# protoboard.net
KiCad netlist of a schematic drawn in EAGLE
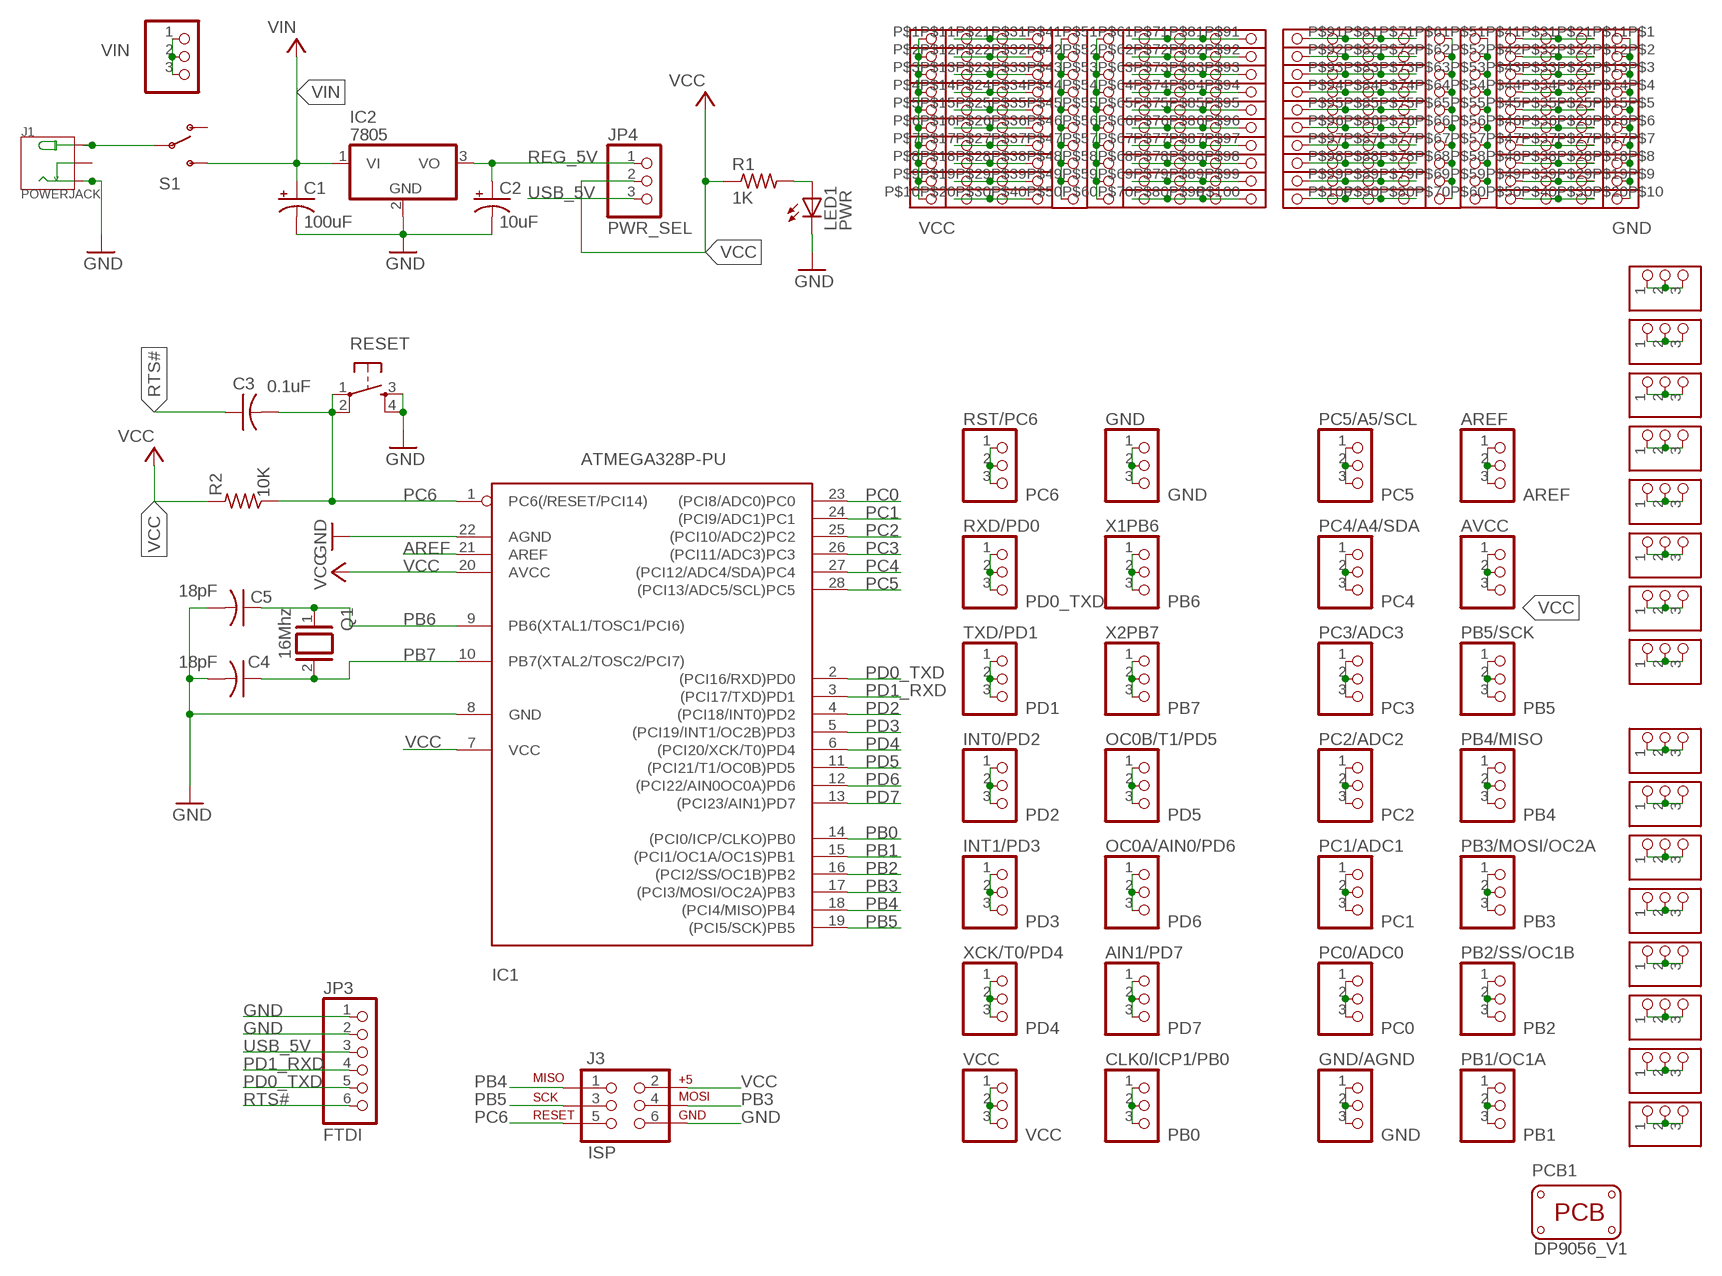
[diagram p0: schematic, sheet 1]

(export (version "E")
  (design (tool "Eeschema 10.0.6"))
  (components
    (comp (ref "AIN1/PD7")
      (value "PINHD-1X3")
      (footprint "eagle-import:1X03")
      (libsource (lib "eagle-import") (part "ubiyubix_PINHD-1X3"))
    )
    (comp (ref "AREF")
      (value "PINHD-1X3")
      (footprint "eagle-import:1X03")
      (libsource (lib "eagle-import") (part "ubiyubix_PINHD-1X3"))
    )
    (comp (ref "AVCC")
      (value "PINHD-1X3")
      (footprint "eagle-import:1X03")
      (libsource (lib "eagle-import") (part "ubiyubix_PINHD-1X3"))
    )
    (comp (ref "C1")
      (value "100uF")
      (footprint "eagle-import:CPOL-RADIAL-100UF-25V")
      (libsource (lib "eagle-import") (part "CAP_POLPTH1"))
    )
    (comp (ref "C2")
      (value "10uF")
      (footprint "eagle-import:CPOL-RADIAL-10UF-25V")
      (libsource (lib "eagle-import") (part "CAP_POLPTH2"))
    )
    (comp (ref "C3")
      (value "0.1uF")
      (footprint "eagle-import:C025-025X050")
      (libsource (lib "eagle-import") (part "C-US025-025X050"))
    )
    (comp (ref "C4")
      (value "18pF")
      (footprint "eagle-import:C025-025X050")
      (libsource (lib "eagle-import") (part "C-US025-025X050"))
    )
    (comp (ref "C5")
      (value "18pF")
      (footprint "eagle-import:C025-025X050")
      (libsource (lib "eagle-import") (part "C-US025-025X050"))
    )
    (comp (ref "CLK0/ICP1/PB0")
      (value "PINHD-1X3")
      (footprint "eagle-import:1X03")
      (libsource (lib "eagle-import") (part "ubiyubix_PINHD-1X3"))
    )
    (comp (ref "GND")
      (value "PINHD-1X3")
      (footprint "eagle-import:1X03")
      (libsource (lib "eagle-import") (part "ubiyubix_PINHD-1X3"))
    )
    (comp (ref "GND/AGND")
      (value "PINHD-1X3")
      (footprint "eagle-import:1X03")
      (libsource (lib "eagle-import") (part "ubiyubix_PINHD-1X3"))
    )
    (comp (ref "IC1")
      (value "ATMEGA328P-PU")
      (footprint "eagle-import:DIL28-3")
      (libsource (lib "eagle-import") (part "ATMEGA168P-20"))
    )
    (comp (ref "IC2")
      (value "7805")
      (footprint "eagle-import:TO220H")
      (libsource (lib "eagle-import") (part "78T05"))
    )
    (comp (ref "INT0/PD2")
      (value "PINHD-1X3")
      (footprint "eagle-import:1X03")
      (libsource (lib "eagle-import") (part "ubiyubix_PINHD-1X3"))
    )
    (comp (ref "INT1/PD3")
      (value "PINHD-1X3")
      (footprint "eagle-import:1X03")
      (libsource (lib "eagle-import") (part "ubiyubix_PINHD-1X3"))
    )
    (comp (ref "J1")
      (value "POWERJACK")
      (footprint "eagle-import:PW-3P-2.1")
      (libsource (lib "eagle-import") (part "JACK-DC-3P-3410020P1"))
    )
    (comp (ref "J3")
      (value "ISP")
      (footprint "eagle-import:2X3")
      (libsource (lib "eagle-import") (part "AVR_SPI_PRG_6PTH"))
    )
    (comp (ref "JP3")
      (value "FTDI")
      (footprint "eagle-import:1X06")
      (libsource (lib "eagle-import") (part "PINHD-1X6"))
    )
    (comp (ref "JP4")
      (value "PWR_SEL")
      (footprint "eagle-import:1X03")
      (libsource (lib "eagle-import") (part "PINHD-1X3"))
    )
    (comp (ref "LED1")
      (value "PWR")
      (footprint "eagle-import:LED3MM")
      (libsource (lib "eagle-import") (part "LED3MM"))
    )
    (comp (ref "OC0A/AIN0/PD6")
      (value "PINHD-1X3")
      (footprint "eagle-import:1X03")
      (libsource (lib "eagle-import") (part "ubiyubix_PINHD-1X3"))
    )
    (comp (ref "OC0B/T1/PD5")
      (value "PINHD-1X3")
      (footprint "eagle-import:1X03")
      (libsource (lib "eagle-import") (part "ubiyubix_PINHD-1X3"))
    )
    (comp (ref "PB1/OC1A")
      (value "PINHD-1X3")
      (footprint "eagle-import:1X03")
      (libsource (lib "eagle-import") (part "ubiyubix_PINHD-1X3"))
    )
    (comp (ref "PB2/SS/OC1B")
      (value "PINHD-1X3")
      (footprint "eagle-import:1X03")
      (libsource (lib "eagle-import") (part "ubiyubix_PINHD-1X3"))
    )
    (comp (ref "PB3/MOSI/OC2A")
      (value "PINHD-1X3")
      (footprint "eagle-import:1X03")
      (libsource (lib "eagle-import") (part "ubiyubix_PINHD-1X3"))
    )
    (comp (ref "PB4/MISO")
      (value "PINHD-1X3")
      (footprint "eagle-import:1X03")
      (libsource (lib "eagle-import") (part "ubiyubix_PINHD-1X3"))
    )
    (comp (ref "PB5/SCK")
      (value "PINHD-1X3")
      (footprint "eagle-import:1X03")
      (libsource (lib "eagle-import") (part "ubiyubix_PINHD-1X3"))
    )
    (comp (ref "PC0/ADC0")
      (value "PINHD-1X3")
      (footprint "eagle-import:1X03")
      (libsource (lib "eagle-import") (part "ubiyubix_PINHD-1X3"))
    )
    (comp (ref "PC1/ADC1")
      (value "PINHD-1X3")
      (footprint "eagle-import:1X03")
      (libsource (lib "eagle-import") (part "ubiyubix_PINHD-1X3"))
    )
    (comp (ref "PC2/ADC2")
      (value "PINHD-1X3")
      (footprint "eagle-import:1X03")
      (libsource (lib "eagle-import") (part "ubiyubix_PINHD-1X3"))
    )
    (comp (ref "PC3/ADC3")
      (value "PINHD-1X3")
      (footprint "eagle-import:1X03")
      (libsource (lib "eagle-import") (part "ubiyubix_PINHD-1X3"))
    )
    (comp (ref "PC4/A4/SDA")
      (value "PINHD-1X3")
      (footprint "eagle-import:1X03")
      (libsource (lib "eagle-import") (part "ubiyubix_PINHD-1X3"))
    )
    (comp (ref "PC5/A5/SCL")
      (value "PINHD-1X3")
      (footprint "eagle-import:1X03")
      (libsource (lib "eagle-import") (part "ubiyubix_PINHD-1X3"))
    )
    (comp (ref "PCB1")
      (value "PCB_DP_RECTANGLE-56X90")
      (footprint "eagle-import:DP9056_V1")
      (libsource (lib "eagle-import") (part "PCB_DP_RECTANGLE-56X90"))
    )
    (comp (ref "Q1")
      (value "16Mhz")
      (footprint "eagle-import:QS")
      (libsource (lib "eagle-import") (part "XTAL/S"))
    )
    (comp (ref "R1")
      (value "1K")
      (footprint "eagle-import:0207_7")
      (libsource (lib "eagle-import") (part "RESISTOR-1/4W"))
    )
    (comp (ref "R2")
      (value "10K")
      (footprint "eagle-import:0207_7")
      (libsource (lib "eagle-import") (part "RESISTOR-1/4W"))
    )
    (comp (ref "RESET")
      (value "TAC_SWITCHPTH")
      (footprint "eagle-import:TACTILE-PTH")
      (libsource (lib "eagle-import") (part "TAC_SWITCHPTH"))
    )
    (comp (ref "RST/PC6")
      (value "PINHD-1X3")
      (footprint "eagle-import:1X03")
      (libsource (lib "eagle-import") (part "ubiyubix_PINHD-1X3"))
    )
    (comp (ref "RXD/PD0")
      (value "PINHD-1X3")
      (footprint "eagle-import:1X03")
      (libsource (lib "eagle-import") (part "ubiyubix_PINHD-1X3"))
    )
    (comp (ref "S1")
      (value "SWITCH-SPDTPTH")
      (footprint "eagle-import:SWITCH-SPDT")
      (libsource (lib "eagle-import") (part "SWITCH-SPDTPTH"))
    )
    (comp (ref "TXD/PD1")
      (value "PINHD-1X3")
      (footprint "eagle-import:1X03")
      (libsource (lib "eagle-import") (part "ubiyubix_PINHD-1X3"))
    )
    (comp (ref "U$1")
      (value "PROTOFIELD-10X10")
      (footprint "eagle-import:PROTOFIELD-10X10")
      (libsource (lib "eagle-import") (part "PROTOFIELD-10X10"))
    )
    (comp (ref "U$3")
      (value "PROTOFIELD-10X10")
      (footprint "eagle-import:PROTOFIELD-10X10")
      (libsource (lib "eagle-import") (part "PROTOFIELD-10X10"))
    )
    (comp (ref "U$4")
      (value "PROTOFIELD-3")
      (footprint "eagle-import:PROTOFIELD-3")
      (libsource (lib "eagle-import") (part "PROTOFIELD-3"))
    )
    (comp (ref "U$5")
      (value "PROTOFIELD-3")
      (footprint "eagle-import:PROTOFIELD-3")
      (libsource (lib "eagle-import") (part "PROTOFIELD-3"))
    )
    (comp (ref "U$6")
      (value "PROTOFIELD-3")
      (footprint "eagle-import:PROTOFIELD-3")
      (libsource (lib "eagle-import") (part "PROTOFIELD-3"))
    )
    (comp (ref "U$7")
      (value "PROTOFIELD-3")
      (footprint "eagle-import:PROTOFIELD-3")
      (libsource (lib "eagle-import") (part "PROTOFIELD-3"))
    )
    (comp (ref "U$8")
      (value "PROTOFIELD-3")
      (footprint "eagle-import:PROTOFIELD-3")
      (libsource (lib "eagle-import") (part "PROTOFIELD-3"))
    )
    (comp (ref "U$9")
      (value "PROTOFIELD-3")
      (footprint "eagle-import:PROTOFIELD-3")
      (libsource (lib "eagle-import") (part "PROTOFIELD-3"))
    )
    (comp (ref "U$10")
      (value "PROTOFIELD-3")
      (footprint "eagle-import:PROTOFIELD-3")
      (libsource (lib "eagle-import") (part "PROTOFIELD-3"))
    )
    (comp (ref "U$11")
      (value "PROTOFIELD-3")
      (footprint "eagle-import:PROTOFIELD-3")
      (libsource (lib "eagle-import") (part "PROTOFIELD-3"))
    )
    (comp (ref "U$12")
      (value "PROTOFIELD-3")
      (footprint "eagle-import:PROTOFIELD-3")
      (libsource (lib "eagle-import") (part "PROTOFIELD-3"))
    )
    (comp (ref "U$13")
      (value "PROTOFIELD-3")
      (footprint "eagle-import:PROTOFIELD-3")
      (libsource (lib "eagle-import") (part "PROTOFIELD-3"))
    )
    (comp (ref "U$14")
      (value "PROTOFIELD-3")
      (footprint "eagle-import:PROTOFIELD-3")
      (libsource (lib "eagle-import") (part "PROTOFIELD-3"))
    )
    (comp (ref "U$15")
      (value "PROTOFIELD-3")
      (footprint "eagle-import:PROTOFIELD-3")
      (libsource (lib "eagle-import") (part "PROTOFIELD-3"))
    )
    (comp (ref "U$16")
      (value "PROTOFIELD-3")
      (footprint "eagle-import:PROTOFIELD-3")
      (libsource (lib "eagle-import") (part "PROTOFIELD-3"))
    )
    (comp (ref "U$17")
      (value "PROTOFIELD-3")
      (footprint "eagle-import:PROTOFIELD-3")
      (libsource (lib "eagle-import") (part "PROTOFIELD-3"))
    )
    (comp (ref "U$18")
      (value "PROTOFIELD-3")
      (footprint "eagle-import:PROTOFIELD-3")
      (libsource (lib "eagle-import") (part "PROTOFIELD-3"))
    )
    (comp (ref "U$19")
      (value "PROTOFIELD-3")
      (footprint "eagle-import:PROTOFIELD-3")
      (libsource (lib "eagle-import") (part "PROTOFIELD-3"))
    )
    (comp (ref "VCC")
      (value "PINHD-1X3")
      (footprint "eagle-import:1X03")
      (libsource (lib "eagle-import") (part "ubiyubix_PINHD-1X3"))
    )
    (comp (ref "VIN")
      (value "+9V")
      (footprint "eagle-import:1X03")
      (libsource (lib "eagle-import") (part "ubiyubix_PINHD-1X3"))
    )
    (comp (ref "X1PB6")
      (value "PINHD-1X3")
      (footprint "eagle-import:1X03")
      (libsource (lib "eagle-import") (part "ubiyubix_PINHD-1X3"))
    )
    (comp (ref "X2PB7")
      (value "PINHD-1X3")
      (footprint "eagle-import:1X03")
      (libsource (lib "eagle-import") (part "ubiyubix_PINHD-1X3"))
    )
    (comp (ref "XCK/T0/PD4")
      (value "PINHD-1X3")
      (footprint "eagle-import:1X03")
      (libsource (lib "eagle-import") (part "ubiyubix_PINHD-1X3"))
    )
  )
  (nets
    (net (code "1") (name "/AREF") (class "Default")
      (node (ref "AREF") (pin "1") (pinfunction "1_1") (pintype "passive"))
      (node (ref "AREF") (pin "2") (pinfunction "2_2") (pintype "passive"))
      (node (ref "AREF") (pin "3") (pinfunction "3_3") (pintype "passive"))
      (node (ref "IC1") (pin "21") (pinfunction "AREF_21") (pintype "bidirectional"))
    )
    (net (code "2") (name "/PB0") (class "Default")
      (node (ref "CLK0/ICP1/PB0") (pin "1") (pinfunction "1_1") (pintype "passive"))
      (node (ref "CLK0/ICP1/PB0") (pin "2") (pinfunction "2_2") (pintype "passive"))
      (node (ref "CLK0/ICP1/PB0") (pin "3") (pinfunction "3_3") (pintype "passive"))
      (node (ref "IC1") (pin "14") (pinfunction "(PCI0/ICP/CLKO)PB0_14") (pintype "bidirectional"))
    )
    (net (code "3") (name "/PB1") (class "Default")
      (node (ref "IC1") (pin "15") (pinfunction "(PCI1/OC1A/OC1S)PB1_15") (pintype "bidirectional"))
      (node (ref "PB1/OC1A") (pin "1") (pinfunction "1_1") (pintype "passive"))
      (node (ref "PB1/OC1A") (pin "2") (pinfunction "2_2") (pintype "passive"))
      (node (ref "PB1/OC1A") (pin "3") (pinfunction "3_3") (pintype "passive"))
    )
    (net (code "4") (name "/PB2") (class "Default")
      (node (ref "IC1") (pin "16") (pinfunction "(PCI2/SS/OC1B)PB2_16") (pintype "bidirectional"))
      (node (ref "PB2/SS/OC1B") (pin "1") (pinfunction "1_1") (pintype "passive"))
      (node (ref "PB2/SS/OC1B") (pin "2") (pinfunction "2_2") (pintype "passive"))
      (node (ref "PB2/SS/OC1B") (pin "3") (pinfunction "3_3") (pintype "passive"))
    )
    (net (code "5") (name "/PB3") (class "Default")
      (node (ref "IC1") (pin "17") (pinfunction "(PCI3/MOSI/OC2A)PB3_17") (pintype "bidirectional"))
      (node (ref "J3") (pin "4") (pinfunction "4_4") (pintype "passive"))
      (node (ref "PB3/MOSI/OC2A") (pin "1") (pinfunction "1_1") (pintype "passive"))
      (node (ref "PB3/MOSI/OC2A") (pin "2") (pinfunction "2_2") (pintype "passive"))
      (node (ref "PB3/MOSI/OC2A") (pin "3") (pinfunction "3_3") (pintype "passive"))
    )
    (net (code "6") (name "/PB4") (class "Default")
      (node (ref "IC1") (pin "18") (pinfunction "(PCI4/MISO)PB4_18") (pintype "bidirectional"))
      (node (ref "J3") (pin "1") (pinfunction "1_1") (pintype "passive"))
      (node (ref "PB4/MISO") (pin "1") (pinfunction "1_1") (pintype "passive"))
      (node (ref "PB4/MISO") (pin "2") (pinfunction "2_2") (pintype "passive"))
      (node (ref "PB4/MISO") (pin "3") (pinfunction "3_3") (pintype "passive"))
    )
    (net (code "7") (name "/PB5") (class "Default")
      (node (ref "IC1") (pin "19") (pinfunction "(PCI5/SCK)PB5_19") (pintype "bidirectional"))
      (node (ref "J3") (pin "3") (pinfunction "3_3") (pintype "passive"))
      (node (ref "PB5/SCK") (pin "1") (pinfunction "1_1") (pintype "passive"))
      (node (ref "PB5/SCK") (pin "2") (pinfunction "2_2") (pintype "passive"))
      (node (ref "PB5/SCK") (pin "3") (pinfunction "3_3") (pintype "passive"))
    )
    (net (code "8") (name "/PB6") (class "Default")
      (node (ref "C5") (pin "1") (pinfunction "1_1") (pintype "passive"))
      (node (ref "IC1") (pin "9") (pinfunction "PB6(XTAL1/TOSC1/PCI6)_9") (pintype "bidirectional"))
      (node (ref "Q1") (pin "1") (pinfunction "1_1") (pintype "passive"))
      (node (ref "X1PB6") (pin "1") (pinfunction "1_1") (pintype "passive"))
      (node (ref "X1PB6") (pin "2") (pinfunction "2_2") (pintype "passive"))
      (node (ref "X1PB6") (pin "3") (pinfunction "3_3") (pintype "passive"))
    )
    (net (code "9") (name "/PB7") (class "Default")
      (node (ref "C4") (pin "1") (pinfunction "1_1") (pintype "passive"))
      (node (ref "IC1") (pin "10") (pinfunction "PB7(XTAL2/TOSC2/PCI7)_10") (pintype "bidirectional"))
      (node (ref "Q1") (pin "2") (pinfunction "2_2") (pintype "passive"))
      (node (ref "X2PB7") (pin "1") (pinfunction "1_1") (pintype "passive"))
      (node (ref "X2PB7") (pin "2") (pinfunction "2_2") (pintype "passive"))
      (node (ref "X2PB7") (pin "3") (pinfunction "3_3") (pintype "passive"))
    )
    (net (code "10") (name "/PC0") (class "Default")
      (node (ref "IC1") (pin "23") (pinfunction "(PCI8/ADC0)PC0_23") (pintype "bidirectional"))
      (node (ref "PC0/ADC0") (pin "1") (pinfunction "1_1") (pintype "passive"))
      (node (ref "PC0/ADC0") (pin "2") (pinfunction "2_2") (pintype "passive"))
      (node (ref "PC0/ADC0") (pin "3") (pinfunction "3_3") (pintype "passive"))
    )
    (net (code "11") (name "/PC1") (class "Default")
      (node (ref "IC1") (pin "24") (pinfunction "(PCI9/ADC1)PC1_24") (pintype "bidirectional"))
      (node (ref "PC1/ADC1") (pin "1") (pinfunction "1_1") (pintype "passive"))
      (node (ref "PC1/ADC1") (pin "2") (pinfunction "2_2") (pintype "passive"))
      (node (ref "PC1/ADC1") (pin "3") (pinfunction "3_3") (pintype "passive"))
    )
    (net (code "12") (name "/PC2") (class "Default")
      (node (ref "IC1") (pin "25") (pinfunction "(PCI10/ADC2)PC2_25") (pintype "bidirectional"))
      (node (ref "PC2/ADC2") (pin "1") (pinfunction "1_1") (pintype "passive"))
      (node (ref "PC2/ADC2") (pin "2") (pinfunction "2_2") (pintype "passive"))
      (node (ref "PC2/ADC2") (pin "3") (pinfunction "3_3") (pintype "passive"))
    )
    (net (code "13") (name "/PC3") (class "Default")
      (node (ref "IC1") (pin "26") (pinfunction "(PCI11/ADC3)PC3_26") (pintype "bidirectional"))
      (node (ref "PC3/ADC3") (pin "1") (pinfunction "1_1") (pintype "passive"))
      (node (ref "PC3/ADC3") (pin "2") (pinfunction "2_2") (pintype "passive"))
      (node (ref "PC3/ADC3") (pin "3") (pinfunction "3_3") (pintype "passive"))
    )
    (net (code "14") (name "/PC4") (class "Default")
      (node (ref "IC1") (pin "27") (pinfunction "(PCI12/ADC4/SDA)PC4_27") (pintype "bidirectional"))
      (node (ref "PC4/A4/SDA") (pin "1") (pinfunction "1_1") (pintype "passive"))
      (node (ref "PC4/A4/SDA") (pin "2") (pinfunction "2_2") (pintype "passive"))
      (node (ref "PC4/A4/SDA") (pin "3") (pinfunction "3_3") (pintype "passive"))
    )
    (net (code "15") (name "/PC5") (class "Default")
      (node (ref "IC1") (pin "28") (pinfunction "(PCI13/ADC5/SCL)PC5_28") (pintype "bidirectional"))
      (node (ref "PC5/A5/SCL") (pin "1") (pinfunction "1_1") (pintype "passive"))
      (node (ref "PC5/A5/SCL") (pin "2") (pinfunction "2_2") (pintype "passive"))
      (node (ref "PC5/A5/SCL") (pin "3") (pinfunction "3_3") (pintype "passive"))
    )
    (net (code "16") (name "/PC6") (class "Default")
      (node (ref "C3") (pin "2") (pinfunction "2_2") (pintype "passive"))
      (node (ref "IC1") (pin "1") (pinfunction "PC6(/RESET/PCI14)_1") (pintype "bidirectional"))
      (node (ref "J3") (pin "5") (pinfunction "5_5") (pintype "passive"))
      (node (ref "R2") (pin "1") (pinfunction "1_1") (pintype "passive"))
      (node (ref "RESET") (pin "1") (pinfunction "1_1") (pintype "passive"))
      (node (ref "RESET") (pin "2") (pinfunction "2_2") (pintype "passive"))
      (node (ref "RST/PC6") (pin "1") (pinfunction "1_1") (pintype "passive"))
      (node (ref "RST/PC6") (pin "2") (pinfunction "2_2") (pintype "passive"))
      (node (ref "RST/PC6") (pin "3") (pinfunction "3_3") (pintype "passive"))
    )
    (net (code "17") (name "/PD0_TXD") (class "Default")
      (node (ref "IC1") (pin "2") (pinfunction "(PCI16/RXD)PD0_2") (pintype "bidirectional"))
      (node (ref "JP3") (pin "5") (pinfunction "5_5") (pintype "passive"))
      (node (ref "RXD/PD0") (pin "1") (pinfunction "1_1") (pintype "passive"))
      (node (ref "RXD/PD0") (pin "2") (pinfunction "2_2") (pintype "passive"))
      (node (ref "RXD/PD0") (pin "3") (pinfunction "3_3") (pintype "passive"))
    )
    (net (code "18") (name "/PD1") (class "Default")
      (node (ref "TXD/PD1") (pin "1") (pinfunction "1_1") (pintype "passive"))
      (node (ref "TXD/PD1") (pin "2") (pinfunction "2_2") (pintype "passive"))
      (node (ref "TXD/PD1") (pin "3") (pinfunction "3_3") (pintype "passive"))
    )
    (net (code "19") (name "/PD1_RXD") (class "Default")
      (node (ref "IC1") (pin "3") (pinfunction "(PCI17/TXD)PD1_3") (pintype "bidirectional"))
      (node (ref "JP3") (pin "4") (pinfunction "4_4") (pintype "passive"))
    )
    (net (code "20") (name "/PD2") (class "Default")
      (node (ref "IC1") (pin "4") (pinfunction "(PCI18/INT0)PD2_4") (pintype "bidirectional"))
      (node (ref "INT0/PD2") (pin "1") (pinfunction "1_1") (pintype "passive"))
      (node (ref "INT0/PD2") (pin "2") (pinfunction "2_2") (pintype "passive"))
      (node (ref "INT0/PD2") (pin "3") (pinfunction "3_3") (pintype "passive"))
    )
    (net (code "21") (name "/PD3") (class "Default")
      (node (ref "IC1") (pin "5") (pinfunction "(PCI19/INT1/OC2B)PD3_5") (pintype "bidirectional"))
      (node (ref "INT1/PD3") (pin "1") (pinfunction "1_1") (pintype "passive"))
      (node (ref "INT1/PD3") (pin "2") (pinfunction "2_2") (pintype "passive"))
      (node (ref "INT1/PD3") (pin "3") (pinfunction "3_3") (pintype "passive"))
    )
    (net (code "22") (name "/PD4") (class "Default")
      (node (ref "IC1") (pin "6") (pinfunction "(PCI20/XCK/T0)PD4_6") (pintype "bidirectional"))
      (node (ref "XCK/T0/PD4") (pin "1") (pinfunction "1_1") (pintype "passive"))
      (node (ref "XCK/T0/PD4") (pin "2") (pinfunction "2_2") (pintype "passive"))
      (node (ref "XCK/T0/PD4") (pin "3") (pinfunction "3_3") (pintype "passive"))
    )
    (net (code "23") (name "/PD5") (class "Default")
      (node (ref "IC1") (pin "11") (pinfunction "(PCI21/T1/OC0B)PD5_11") (pintype "bidirectional"))
      (node (ref "OC0B/T1/PD5") (pin "1") (pinfunction "1_1") (pintype "passive"))
      (node (ref "OC0B/T1/PD5") (pin "2") (pinfunction "2_2") (pintype "passive"))
      (node (ref "OC0B/T1/PD5") (pin "3") (pinfunction "3_3") (pintype "passive"))
    )
    (net (code "24") (name "/PD6") (class "Default")
      (node (ref "IC1") (pin "12") (pinfunction "(PCI22/AIN0OC0A)PD6_12") (pintype "bidirectional"))
      (node (ref "OC0A/AIN0/PD6") (pin "1") (pinfunction "1_1") (pintype "passive"))
      (node (ref "OC0A/AIN0/PD6") (pin "2") (pinfunction "2_2") (pintype "passive"))
      (node (ref "OC0A/AIN0/PD6") (pin "3") (pinfunction "3_3") (pintype "passive"))
    )
    (net (code "25") (name "/PD7") (class "Default")
      (node (ref "AIN1/PD7") (pin "1") (pinfunction "1_1") (pintype "passive"))
      (node (ref "AIN1/PD7") (pin "2") (pinfunction "2_2") (pintype "passive"))
      (node (ref "AIN1/PD7") (pin "3") (pinfunction "3_3") (pintype "passive"))
      (node (ref "IC1") (pin "13") (pinfunction "(PCI23/AIN1)PD7_13") (pintype "bidirectional"))
    )
    (net (code "26") (name "/REG_5V") (class "Default")
      (node (ref "C2") (pin "1") (pinfunction "+_1") (pintype "passive"))
      (node (ref "IC2") (pin "3") (pinfunction "VO_3") (pintype "passive"))
      (node (ref "JP4") (pin "1") (pinfunction "1_1") (pintype "passive"))
    )
    (net (code "27") (name "/USB_5V") (class "Default")
      (node (ref "JP3") (pin "3") (pinfunction "3_3") (pintype "passive"))
      (node (ref "JP4") (pin "3") (pinfunction "3_3") (pintype "passive"))
    )
    (net (code "28") (name "GND") (class "Default")
      (node (ref "C1") (pin "2") (pinfunction "-_2") (pintype "passive"))
      (node (ref "C2") (pin "2") (pinfunction "-_2") (pintype "passive"))
      (node (ref "C4") (pin "2") (pinfunction "2_2") (pintype "passive"))
      (node (ref "C5") (pin "2") (pinfunction "2_2") (pintype "passive"))
      (node (ref "GND") (pin "1") (pinfunction "1_1") (pintype "passive"))
      (node (ref "GND") (pin "2") (pinfunction "2_2") (pintype "passive"))
      (node (ref "GND") (pin "3") (pinfunction "3_3") (pintype "passive"))
      (node (ref "GND/AGND") (pin "1") (pinfunction "1_1") (pintype "passive"))
      (node (ref "GND/AGND") (pin "2") (pinfunction "2_2") (pintype "passive"))
      (node (ref "GND/AGND") (pin "3") (pinfunction "3_3") (pintype "passive"))
      (node (ref "IC1") (pin "22") (pinfunction "AGND_22") (pintype "bidirectional"))
      (node (ref "IC1") (pin "8") (pinfunction "GND_8") (pintype "bidirectional"))
      (node (ref "IC2") (pin "2") (pinfunction "GND_2") (pintype "passive"))
      (node (ref "J1") (pin "-1") (pinfunction "-_-1") (pintype "bidirectional"))
      (node (ref "J3") (pin "6") (pinfunction "6_6") (pintype "passive"))
      (node (ref "JP3") (pin "1") (pinfunction "1_1") (pintype "passive"))
      (node (ref "JP3") (pin "2") (pinfunction "2_2") (pintype "passive"))
      (node (ref "LED1") (pin "K") (pinfunction "C_K") (pintype "passive"))
      (node (ref "RESET") (pin "3") (pinfunction "3_3") (pintype "passive"))
      (node (ref "RESET") (pin "4") (pinfunction "4_4") (pintype "passive"))
      (node (ref "U$3") (pin "P$1") (pinfunction "1_P$1") (pintype "passive"))
      (node (ref "U$3") (pin "P$10") (pinfunction "P$10_P$10") (pintype "passive"))
      (node (ref "U$3") (pin "P$2") (pinfunction "5_P$2") (pintype "passive"))
      (node (ref "U$3") (pin "P$3") (pinfunction "P$3_P$3") (pintype "passive"))
      (node (ref "U$3") (pin "P$4") (pinfunction "P$4_P$4") (pintype "passive"))
      (node (ref "U$3") (pin "P$5") (pinfunction "P$5_P$5") (pintype "passive"))
      (node (ref "U$3") (pin "P$6") (pinfunction "P$6_P$6") (pintype "passive"))
      (node (ref "U$3") (pin "P$7") (pinfunction "P$7_P$7") (pintype "passive"))
      (node (ref "U$3") (pin "P$8") (pinfunction "P$8_P$8") (pintype "passive"))
      (node (ref "U$3") (pin "P$9") (pinfunction "P$9_P$9") (pintype "passive"))
    )
    (net (code "29") (name "Net-(LED1-PadA)") (class "Default")
      (node (ref "LED1") (pin "A") (pinfunction "A_A") (pintype "passive"))
      (node (ref "R1") (pin "2") (pinfunction "2_2") (pintype "passive"))
    )
    (net (code "30") (name "Net-(S1-P)") (class "Default")
      (node (ref "J1") (pin "+") (pinfunction "+_+") (pintype "bidirectional"))
      (node (ref "S1") (pin "2") (pinfunction "P_2") (pintype "passive"))
    )
    (net (code "31") (name "Net-(U$1-2)") (class "Default")
      (node (ref "U$1") (pin "P$11") (pinfunction "2_P$11") (pintype "passive"))
      (node (ref "U$1") (pin "P$21") (pinfunction "3_P$21") (pintype "passive"))
      (node (ref "U$1") (pin "P$31") (pinfunction "4_P$31") (pintype "passive"))
    )
    (net (code "32") (name "Net-(U$1-6)") (class "Default")
      (node (ref "U$1") (pin "P$12") (pinfunction "6_P$12") (pintype "passive"))
      (node (ref "U$1") (pin "P$22") (pinfunction "7_P$22") (pintype "passive"))
      (node (ref "U$1") (pin "P$32") (pinfunction "8_P$32") (pintype "passive"))
    )
    (net (code "33") (name "Net-(U$1-PadP$13)") (class "Default")
      (node (ref "U$1") (pin "P$13") (pinfunction "P$13_P$13") (pintype "passive"))
      (node (ref "U$1") (pin "P$23") (pinfunction "P$23_P$23") (pintype "passive"))
      (node (ref "U$1") (pin "P$33") (pinfunction "P$33_P$33") (pintype "passive"))
    )
    (net (code "34") (name "Net-(U$1-PadP$14)") (class "Default")
      (node (ref "U$1") (pin "P$14") (pinfunction "P$14_P$14") (pintype "passive"))
      (node (ref "U$1") (pin "P$24") (pinfunction "P$24_P$24") (pintype "passive"))
      (node (ref "U$1") (pin "P$34") (pinfunction "P$34_P$34") (pintype "passive"))
    )
    (net (code "35") (name "Net-(U$1-PadP$15)") (class "Default")
      (node (ref "U$1") (pin "P$15") (pinfunction "P$15_P$15") (pintype "passive"))
      (node (ref "U$1") (pin "P$25") (pinfunction "P$25_P$25") (pintype "passive"))
      (node (ref "U$1") (pin "P$35") (pinfunction "P$35_P$35") (pintype "passive"))
    )
    (net (code "36") (name "Net-(U$1-PadP$16)") (class "Default")
      (node (ref "U$1") (pin "P$16") (pinfunction "P$16_P$16") (pintype "passive"))
      (node (ref "U$1") (pin "P$26") (pinfunction "P$26_P$26") (pintype "passive"))
      (node (ref "U$1") (pin "P$36") (pinfunction "P$36_P$36") (pintype "passive"))
    )
    (net (code "37") (name "Net-(U$1-PadP$17)") (class "Default")
      (node (ref "U$1") (pin "P$17") (pinfunction "P$17_P$17") (pintype "passive"))
      (node (ref "U$1") (pin "P$27") (pinfunction "P$27_P$27") (pintype "passive"))
      (node (ref "U$1") (pin "P$37") (pinfunction "P$37_P$37") (pintype "passive"))
    )
    (net (code "38") (name "Net-(U$1-PadP$18)") (class "Default")
      (node (ref "U$1") (pin "P$18") (pinfunction "P$18_P$18") (pintype "passive"))
      (node (ref "U$1") (pin "P$28") (pinfunction "P$28_P$28") (pintype "passive"))
      (node (ref "U$1") (pin "P$38") (pinfunction "P$38_P$38") (pintype "passive"))
    )
    (net (code "39") (name "Net-(U$1-PadP$19)") (class "Default")
      (node (ref "U$1") (pin "P$19") (pinfunction "P$19_P$19") (pintype "passive"))
      (node (ref "U$1") (pin "P$29") (pinfunction "P$29_P$29") (pintype "passive"))
      (node (ref "U$1") (pin "P$39") (pinfunction "P$39_P$39") (pintype "passive"))
    )
    (net (code "40") (name "Net-(U$1-PadP$20)") (class "Default")
      (node (ref "U$1") (pin "P$20") (pinfunction "P$20_P$20") (pintype "passive"))
      (node (ref "U$1") (pin "P$30") (pinfunction "P$30_P$30") (pintype "passive"))
      (node (ref "U$1") (pin "P$40") (pinfunction "P$40_P$40") (pintype "passive"))
    )
    (net (code "41") (name "Net-(U$1-PadP$41)") (class "Default")
      (node (ref "U$1") (pin "P$41") (pinfunction "P$41_P$41") (pintype "passive"))
      (node (ref "U$1") (pin "P$42") (pinfunction "P$42_P$42") (pintype "passive"))
      (node (ref "U$1") (pin "P$43") (pinfunction "P$43_P$43") (pintype "passive"))
      (node (ref "U$1") (pin "P$44") (pinfunction "P$44_P$44") (pintype "passive"))
      (node (ref "U$1") (pin "P$45") (pinfunction "P$45_P$45") (pintype "passive"))
      (node (ref "U$1") (pin "P$46") (pinfunction "P$46_P$46") (pintype "passive"))
      (node (ref "U$1") (pin "P$47") (pinfunction "P$47_P$47") (pintype "passive"))
      (node (ref "U$1") (pin "P$48") (pinfunction "P$48_P$48") (pintype "passive"))
      (node (ref "U$1") (pin "P$49") (pinfunction "P$49_P$49") (pintype "passive"))
      (node (ref "U$1") (pin "P$50") (pinfunction "P$50_P$50") (pintype "passive"))
    )
    (net (code "42") (name "Net-(U$1-PadP$51)") (class "Default")
      (node (ref "U$1") (pin "P$51") (pinfunction "P$51_P$51") (pintype "passive"))
      (node (ref "U$1") (pin "P$52") (pinfunction "P$52_P$52") (pintype "passive"))
      (node (ref "U$1") (pin "P$53") (pinfunction "P$53_P$53") (pintype "passive"))
      (node (ref "U$1") (pin "P$54") (pinfunction "P$54_P$54") (pintype "passive"))
      (node (ref "U$1") (pin "P$55") (pinfunction "P$55_P$55") (pintype "passive"))
      (node (ref "U$1") (pin "P$56") (pinfunction "P$56_P$56") (pintype "passive"))
      (node (ref "U$1") (pin "P$57") (pinfunction "P$57_P$57") (pintype "passive"))
      (node (ref "U$1") (pin "P$58") (pinfunction "P$58_P$58") (pintype "passive"))
      (node (ref "U$1") (pin "P$59") (pinfunction "P$59_P$59") (pintype "passive"))
      (node (ref "U$1") (pin "P$60") (pinfunction "P$60_P$60") (pintype "passive"))
    )
    (net (code "43") (name "Net-(U$1-PadP$61)") (class "Default")
      (node (ref "U$1") (pin "P$61") (pinfunction "P$61_P$61") (pintype "passive"))
      (node (ref "U$1") (pin "P$71") (pinfunction "P$71_P$71") (pintype "passive"))
      (node (ref "U$1") (pin "P$81") (pinfunction "P$81_P$81") (pintype "passive"))
      (node (ref "U$1") (pin "P$91") (pinfunction "P$91_P$91") (pintype "passive"))
    )
    (net (code "44") (name "Net-(U$1-PadP$62)") (class "Default")
      (node (ref "U$1") (pin "P$62") (pinfunction "P$62_P$62") (pintype "passive"))
      (node (ref "U$1") (pin "P$72") (pinfunction "P$72_P$72") (pintype "passive"))
      (node (ref "U$1") (pin "P$82") (pinfunction "P$82_P$82") (pintype "passive"))
      (node (ref "U$1") (pin "P$92") (pinfunction "P$92_P$92") (pintype "passive"))
    )
    (net (code "45") (name "Net-(U$1-PadP$63)") (class "Default")
      (node (ref "U$1") (pin "P$63") (pinfunction "P$63_P$63") (pintype "passive"))
      (node (ref "U$1") (pin "P$73") (pinfunction "P$73_P$73") (pintype "passive"))
      (node (ref "U$1") (pin "P$83") (pinfunction "P$83_P$83") (pintype "passive"))
      (node (ref "U$1") (pin "P$93") (pinfunction "P$93_P$93") (pintype "passive"))
    )
    (net (code "46") (name "Net-(U$1-PadP$64)") (class "Default")
      (node (ref "U$1") (pin "P$64") (pinfunction "P$64_P$64") (pintype "passive"))
      (node (ref "U$1") (pin "P$74") (pinfunction "P$74_P$74") (pintype "passive"))
      (node (ref "U$1") (pin "P$84") (pinfunction "P$84_P$84") (pintype "passive"))
      (node (ref "U$1") (pin "P$94") (pinfunction "P$94_P$94") (pintype "passive"))
    )
    (net (code "47") (name "Net-(U$1-PadP$65)") (class "Default")
      (node (ref "U$1") (pin "P$65") (pinfunction "P$65_P$65") (pintype "passive"))
      (node (ref "U$1") (pin "P$75") (pinfunction "P$75_P$75") (pintype "passive"))
      (node (ref "U$1") (pin "P$85") (pinfunction "P$85_P$85") (pintype "passive"))
      (node (ref "U$1") (pin "P$95") (pinfunction "P$95_P$95") (pintype "passive"))
    )
    (net (code "48") (name "Net-(U$1-PadP$66)") (class "Default")
      (node (ref "U$1") (pin "P$66") (pinfunction "P$66_P$66") (pintype "passive"))
      (node (ref "U$1") (pin "P$76") (pinfunction "P$76_P$76") (pintype "passive"))
      (node (ref "U$1") (pin "P$86") (pinfunction "P$86_P$86") (pintype "passive"))
      (node (ref "U$1") (pin "P$96") (pinfunction "P$96_P$96") (pintype "passive"))
    )
    (net (code "49") (name "Net-(U$1-PadP$67)") (class "Default")
      (node (ref "U$1") (pin "P$67") (pinfunction "P$67_P$67") (pintype "passive"))
      (node (ref "U$1") (pin "P$77") (pinfunction "P$77_P$77") (pintype "passive"))
      (node (ref "U$1") (pin "P$87") (pinfunction "P$87_P$87") (pintype "passive"))
      (node (ref "U$1") (pin "P$97") (pinfunction "P$97_P$97") (pintype "passive"))
    )
    (net (code "50") (name "Net-(U$1-PadP$68)") (class "Default")
      (node (ref "U$1") (pin "P$68") (pinfunction "P$68_P$68") (pintype "passive"))
      (node (ref "U$1") (pin "P$78") (pinfunction "P$78_P$78") (pintype "passive"))
      (node (ref "U$1") (pin "P$88") (pinfunction "P$88_P$88") (pintype "passive"))
      (node (ref "U$1") (pin "P$98") (pinfunction "P$98_P$98") (pintype "passive"))
    )
    (net (code "51") (name "Net-(U$1-PadP$69)") (class "Default")
      (node (ref "U$1") (pin "P$69") (pinfunction "P$69_P$69") (pintype "passive"))
      (node (ref "U$1") (pin "P$79") (pinfunction "P$79_P$79") (pintype "passive"))
      (node (ref "U$1") (pin "P$89") (pinfunction "P$89_P$89") (pintype "passive"))
      (node (ref "U$1") (pin "P$99") (pinfunction "P$99_P$99") (pintype "passive"))
    )
    (net (code "52") (name "Net-(U$1-PadP$100)") (class "Default")
      (node (ref "U$1") (pin "P$100") (pinfunction "P$100_P$100") (pintype "passive"))
      (node (ref "U$1") (pin "P$70") (pinfunction "P$70_P$70") (pintype "passive"))
      (node (ref "U$1") (pin "P$80") (pinfunction "P$80_P$80") (pintype "passive"))
      (node (ref "U$1") (pin "P$90") (pinfunction "P$90_P$90") (pintype "passive"))
    )
    (net (code "53") (name "Net-(U$3-2)") (class "Default")
      (node (ref "U$3") (pin "P$11") (pinfunction "2_P$11") (pintype "passive"))
      (node (ref "U$3") (pin "P$21") (pinfunction "3_P$21") (pintype "passive"))
      (node (ref "U$3") (pin "P$31") (pinfunction "4_P$31") (pintype "passive"))
    )
    (net (code "54") (name "Net-(U$3-6)") (class "Default")
      (node (ref "U$3") (pin "P$12") (pinfunction "6_P$12") (pintype "passive"))
      (node (ref "U$3") (pin "P$22") (pinfunction "7_P$22") (pintype "passive"))
      (node (ref "U$3") (pin "P$32") (pinfunction "8_P$32") (pintype "passive"))
    )
    (net (code "55") (name "Net-(U$3-PadP$13)") (class "Default")
      (node (ref "U$3") (pin "P$13") (pinfunction "P$13_P$13") (pintype "passive"))
      (node (ref "U$3") (pin "P$23") (pinfunction "P$23_P$23") (pintype "passive"))
      (node (ref "U$3") (pin "P$33") (pinfunction "P$33_P$33") (pintype "passive"))
    )
    (net (code "56") (name "Net-(U$3-PadP$14)") (class "Default")
      (node (ref "U$3") (pin "P$14") (pinfunction "P$14_P$14") (pintype "passive"))
      (node (ref "U$3") (pin "P$24") (pinfunction "P$24_P$24") (pintype "passive"))
      (node (ref "U$3") (pin "P$34") (pinfunction "P$34_P$34") (pintype "passive"))
    )
    (net (code "57") (name "Net-(U$3-PadP$15)") (class "Default")
      (node (ref "U$3") (pin "P$15") (pinfunction "P$15_P$15") (pintype "passive"))
      (node (ref "U$3") (pin "P$25") (pinfunction "P$25_P$25") (pintype "passive"))
      (node (ref "U$3") (pin "P$35") (pinfunction "P$35_P$35") (pintype "passive"))
    )
    (net (code "58") (name "Net-(U$3-PadP$16)") (class "Default")
      (node (ref "U$3") (pin "P$16") (pinfunction "P$16_P$16") (pintype "passive"))
      (node (ref "U$3") (pin "P$26") (pinfunction "P$26_P$26") (pintype "passive"))
      (node (ref "U$3") (pin "P$36") (pinfunction "P$36_P$36") (pintype "passive"))
    )
    (net (code "59") (name "Net-(U$3-PadP$17)") (class "Default")
      (node (ref "U$3") (pin "P$17") (pinfunction "P$17_P$17") (pintype "passive"))
      (node (ref "U$3") (pin "P$27") (pinfunction "P$27_P$27") (pintype "passive"))
      (node (ref "U$3") (pin "P$37") (pinfunction "P$37_P$37") (pintype "passive"))
    )
    (net (code "60") (name "Net-(U$3-PadP$18)") (class "Default")
      (node (ref "U$3") (pin "P$18") (pinfunction "P$18_P$18") (pintype "passive"))
      (node (ref "U$3") (pin "P$28") (pinfunction "P$28_P$28") (pintype "passive"))
      (node (ref "U$3") (pin "P$38") (pinfunction "P$38_P$38") (pintype "passive"))
    )
    (net (code "61") (name "Net-(U$3-PadP$19)") (class "Default")
      (node (ref "U$3") (pin "P$19") (pinfunction "P$19_P$19") (pintype "passive"))
      (node (ref "U$3") (pin "P$29") (pinfunction "P$29_P$29") (pintype "passive"))
      (node (ref "U$3") (pin "P$39") (pinfunction "P$39_P$39") (pintype "passive"))
    )
    (net (code "62") (name "Net-(U$3-PadP$20)") (class "Default")
      (node (ref "U$3") (pin "P$20") (pinfunction "P$20_P$20") (pintype "passive"))
      (node (ref "U$3") (pin "P$30") (pinfunction "P$30_P$30") (pintype "passive"))
      (node (ref "U$3") (pin "P$40") (pinfunction "P$40_P$40") (pintype "passive"))
    )
    (net (code "63") (name "Net-(U$3-PadP$41)") (class "Default")
      (node (ref "U$3") (pin "P$41") (pinfunction "P$41_P$41") (pintype "passive"))
      (node (ref "U$3") (pin "P$42") (pinfunction "P$42_P$42") (pintype "passive"))
      (node (ref "U$3") (pin "P$43") (pinfunction "P$43_P$43") (pintype "passive"))
      (node (ref "U$3") (pin "P$44") (pinfunction "P$44_P$44") (pintype "passive"))
      (node (ref "U$3") (pin "P$45") (pinfunction "P$45_P$45") (pintype "passive"))
      (node (ref "U$3") (pin "P$46") (pinfunction "P$46_P$46") (pintype "passive"))
      (node (ref "U$3") (pin "P$47") (pinfunction "P$47_P$47") (pintype "passive"))
      (node (ref "U$3") (pin "P$48") (pinfunction "P$48_P$48") (pintype "passive"))
      (node (ref "U$3") (pin "P$49") (pinfunction "P$49_P$49") (pintype "passive"))
      (node (ref "U$3") (pin "P$50") (pinfunction "P$50_P$50") (pintype "passive"))
    )
    (net (code "64") (name "Net-(U$3-PadP$51)") (class "Default")
      (node (ref "U$3") (pin "P$51") (pinfunction "P$51_P$51") (pintype "passive"))
      (node (ref "U$3") (pin "P$52") (pinfunction "P$52_P$52") (pintype "passive"))
      (node (ref "U$3") (pin "P$53") (pinfunction "P$53_P$53") (pintype "passive"))
      (node (ref "U$3") (pin "P$54") (pinfunction "P$54_P$54") (pintype "passive"))
      (node (ref "U$3") (pin "P$55") (pinfunction "P$55_P$55") (pintype "passive"))
      (node (ref "U$3") (pin "P$56") (pinfunction "P$56_P$56") (pintype "passive"))
      (node (ref "U$3") (pin "P$57") (pinfunction "P$57_P$57") (pintype "passive"))
      (node (ref "U$3") (pin "P$58") (pinfunction "P$58_P$58") (pintype "passive"))
      (node (ref "U$3") (pin "P$59") (pinfunction "P$59_P$59") (pintype "passive"))
      (node (ref "U$3") (pin "P$60") (pinfunction "P$60_P$60") (pintype "passive"))
    )
    (net (code "65") (name "Net-(U$3-PadP$61)") (class "Default")
      (node (ref "U$3") (pin "P$61") (pinfunction "P$61_P$61") (pintype "passive"))
      (node (ref "U$3") (pin "P$71") (pinfunction "P$71_P$71") (pintype "passive"))
      (node (ref "U$3") (pin "P$81") (pinfunction "P$81_P$81") (pintype "passive"))
      (node (ref "U$3") (pin "P$91") (pinfunction "P$91_P$91") (pintype "passive"))
    )
    (net (code "66") (name "Net-(U$3-PadP$62)") (class "Default")
      (node (ref "U$3") (pin "P$62") (pinfunction "P$62_P$62") (pintype "passive"))
      (node (ref "U$3") (pin "P$72") (pinfunction "P$72_P$72") (pintype "passive"))
      (node (ref "U$3") (pin "P$82") (pinfunction "P$82_P$82") (pintype "passive"))
      (node (ref "U$3") (pin "P$92") (pinfunction "P$92_P$92") (pintype "passive"))
    )
    (net (code "67") (name "Net-(U$3-PadP$63)") (class "Default")
      (node (ref "U$3") (pin "P$63") (pinfunction "P$63_P$63") (pintype "passive"))
      (node (ref "U$3") (pin "P$73") (pinfunction "P$73_P$73") (pintype "passive"))
      (node (ref "U$3") (pin "P$83") (pinfunction "P$83_P$83") (pintype "passive"))
      (node (ref "U$3") (pin "P$93") (pinfunction "P$93_P$93") (pintype "passive"))
    )
    (net (code "68") (name "Net-(U$3-PadP$64)") (class "Default")
      (node (ref "U$3") (pin "P$64") (pinfunction "P$64_P$64") (pintype "passive"))
      (node (ref "U$3") (pin "P$74") (pinfunction "P$74_P$74") (pintype "passive"))
      (node (ref "U$3") (pin "P$84") (pinfunction "P$84_P$84") (pintype "passive"))
      (node (ref "U$3") (pin "P$94") (pinfunction "P$94_P$94") (pintype "passive"))
    )
    (net (code "69") (name "Net-(U$3-PadP$65)") (class "Default")
      (node (ref "U$3") (pin "P$65") (pinfunction "P$65_P$65") (pintype "passive"))
      (node (ref "U$3") (pin "P$75") (pinfunction "P$75_P$75") (pintype "passive"))
      (node (ref "U$3") (pin "P$85") (pinfunction "P$85_P$85") (pintype "passive"))
      (node (ref "U$3") (pin "P$95") (pinfunction "P$95_P$95") (pintype "passive"))
    )
    (net (code "70") (name "Net-(U$3-PadP$66)") (class "Default")
      (node (ref "U$3") (pin "P$66") (pinfunction "P$66_P$66") (pintype "passive"))
      (node (ref "U$3") (pin "P$76") (pinfunction "P$76_P$76") (pintype "passive"))
      (node (ref "U$3") (pin "P$86") (pinfunction "P$86_P$86") (pintype "passive"))
      (node (ref "U$3") (pin "P$96") (pinfunction "P$96_P$96") (pintype "passive"))
    )
    (net (code "71") (name "Net-(U$3-PadP$67)") (class "Default")
      (node (ref "U$3") (pin "P$67") (pinfunction "P$67_P$67") (pintype "passive"))
      (node (ref "U$3") (pin "P$77") (pinfunction "P$77_P$77") (pintype "passive"))
      (node (ref "U$3") (pin "P$87") (pinfunction "P$87_P$87") (pintype "passive"))
      (node (ref "U$3") (pin "P$97") (pinfunction "P$97_P$97") (pintype "passive"))
    )
    (net (code "72") (name "Net-(U$3-PadP$68)") (class "Default")
      (node (ref "U$3") (pin "P$68") (pinfunction "P$68_P$68") (pintype "passive"))
      (node (ref "U$3") (pin "P$78") (pinfunction "P$78_P$78") (pintype "passive"))
      (node (ref "U$3") (pin "P$88") (pinfunction "P$88_P$88") (pintype "passive"))
      (node (ref "U$3") (pin "P$98") (pinfunction "P$98_P$98") (pintype "passive"))
    )
    (net (code "73") (name "Net-(U$3-PadP$69)") (class "Default")
      (node (ref "U$3") (pin "P$69") (pinfunction "P$69_P$69") (pintype "passive"))
      (node (ref "U$3") (pin "P$79") (pinfunction "P$79_P$79") (pintype "passive"))
      (node (ref "U$3") (pin "P$89") (pinfunction "P$89_P$89") (pintype "passive"))
      (node (ref "U$3") (pin "P$99") (pinfunction "P$99_P$99") (pintype "passive"))
    )
    (net (code "74") (name "Net-(U$3-PadP$100)") (class "Default")
      (node (ref "U$3") (pin "P$100") (pinfunction "P$100_P$100") (pintype "passive"))
      (node (ref "U$3") (pin "P$70") (pinfunction "P$70_P$70") (pintype "passive"))
      (node (ref "U$3") (pin "P$80") (pinfunction "P$80_P$80") (pintype "passive"))
      (node (ref "U$3") (pin "P$90") (pinfunction "P$90_P$90") (pintype "passive"))
    )
    (net (code "75") (name "Net-(U$4-Pad1)") (class "Default")
      (node (ref "U$4") (pin "1") (pinfunction "1_1") (pintype "bidirectional"))
      (node (ref "U$4") (pin "2") (pinfunction "2_2") (pintype "bidirectional"))
      (node (ref "U$4") (pin "3") (pinfunction "3_3") (pintype "bidirectional"))
    )
    (net (code "76") (name "Net-(U$5-Pad1)") (class "Default")
      (node (ref "U$5") (pin "1") (pinfunction "1_1") (pintype "bidirectional"))
      (node (ref "U$5") (pin "2") (pinfunction "2_2") (pintype "bidirectional"))
      (node (ref "U$5") (pin "3") (pinfunction "3_3") (pintype "bidirectional"))
    )
    (net (code "77") (name "Net-(U$6-Pad1)") (class "Default")
      (node (ref "U$6") (pin "1") (pinfunction "1_1") (pintype "bidirectional"))
      (node (ref "U$6") (pin "2") (pinfunction "2_2") (pintype "bidirectional"))
      (node (ref "U$6") (pin "3") (pinfunction "3_3") (pintype "bidirectional"))
    )
    (net (code "78") (name "Net-(U$7-Pad1)") (class "Default")
      (node (ref "U$7") (pin "1") (pinfunction "1_1") (pintype "bidirectional"))
      (node (ref "U$7") (pin "2") (pinfunction "2_2") (pintype "bidirectional"))
      (node (ref "U$7") (pin "3") (pinfunction "3_3") (pintype "bidirectional"))
    )
    (net (code "79") (name "Net-(U$8-Pad1)") (class "Default")
      (node (ref "U$8") (pin "1") (pinfunction "1_1") (pintype "bidirectional"))
      (node (ref "U$8") (pin "2") (pinfunction "2_2") (pintype "bidirectional"))
      (node (ref "U$8") (pin "3") (pinfunction "3_3") (pintype "bidirectional"))
    )
    (net (code "80") (name "Net-(U$9-Pad1)") (class "Default")
      (node (ref "U$9") (pin "1") (pinfunction "1_1") (pintype "bidirectional"))
      (node (ref "U$9") (pin "2") (pinfunction "2_2") (pintype "bidirectional"))
      (node (ref "U$9") (pin "3") (pinfunction "3_3") (pintype "bidirectional"))
    )
    (net (code "81") (name "Net-(U$10-Pad1)") (class "Default")
      (node (ref "U$10") (pin "1") (pinfunction "1_1") (pintype "bidirectional"))
      (node (ref "U$10") (pin "2") (pinfunction "2_2") (pintype "bidirectional"))
      (node (ref "U$10") (pin "3") (pinfunction "3_3") (pintype "bidirectional"))
    )
    (net (code "82") (name "Net-(U$11-Pad1)") (class "Default")
      (node (ref "U$11") (pin "1") (pinfunction "1_1") (pintype "bidirectional"))
      (node (ref "U$11") (pin "2") (pinfunction "2_2") (pintype "bidirectional"))
      (node (ref "U$11") (pin "3") (pinfunction "3_3") (pintype "bidirectional"))
    )
    (net (code "83") (name "Net-(U$12-Pad1)") (class "Default")
      (node (ref "U$12") (pin "1") (pinfunction "1_1") (pintype "bidirectional"))
      (node (ref "U$12") (pin "2") (pinfunction "2_2") (pintype "bidirectional"))
      (node (ref "U$12") (pin "3") (pinfunction "3_3") (pintype "bidirectional"))
    )
    (net (code "84") (name "Net-(U$13-Pad1)") (class "Default")
      (node (ref "U$13") (pin "1") (pinfunction "1_1") (pintype "bidirectional"))
      (node (ref "U$13") (pin "2") (pinfunction "2_2") (pintype "bidirectional"))
      (node (ref "U$13") (pin "3") (pinfunction "3_3") (pintype "bidirectional"))
    )
    (net (code "85") (name "Net-(U$14-Pad1)") (class "Default")
      (node (ref "U$14") (pin "1") (pinfunction "1_1") (pintype "bidirectional"))
      (node (ref "U$14") (pin "2") (pinfunction "2_2") (pintype "bidirectional"))
      (node (ref "U$14") (pin "3") (pinfunction "3_3") (pintype "bidirectional"))
    )
    (net (code "86") (name "Net-(U$15-Pad1)") (class "Default")
      (node (ref "U$15") (pin "1") (pinfunction "1_1") (pintype "bidirectional"))
      (node (ref "U$15") (pin "2") (pinfunction "2_2") (pintype "bidirectional"))
      (node (ref "U$15") (pin "3") (pinfunction "3_3") (pintype "bidirectional"))
    )
    (net (code "87") (name "Net-(U$16-Pad1)") (class "Default")
      (node (ref "U$16") (pin "1") (pinfunction "1_1") (pintype "bidirectional"))
      (node (ref "U$16") (pin "2") (pinfunction "2_2") (pintype "bidirectional"))
      (node (ref "U$16") (pin "3") (pinfunction "3_3") (pintype "bidirectional"))
    )
    (net (code "88") (name "Net-(U$17-Pad1)") (class "Default")
      (node (ref "U$17") (pin "1") (pinfunction "1_1") (pintype "bidirectional"))
      (node (ref "U$17") (pin "2") (pinfunction "2_2") (pintype "bidirectional"))
      (node (ref "U$17") (pin "3") (pinfunction "3_3") (pintype "bidirectional"))
    )
    (net (code "89") (name "Net-(U$18-Pad1)") (class "Default")
      (node (ref "U$18") (pin "1") (pinfunction "1_1") (pintype "bidirectional"))
      (node (ref "U$18") (pin "2") (pinfunction "2_2") (pintype "bidirectional"))
      (node (ref "U$18") (pin "3") (pinfunction "3_3") (pintype "bidirectional"))
    )
    (net (code "90") (name "Net-(U$19-Pad1)") (class "Default")
      (node (ref "U$19") (pin "1") (pinfunction "1_1") (pintype "bidirectional"))
      (node (ref "U$19") (pin "2") (pinfunction "2_2") (pintype "bidirectional"))
      (node (ref "U$19") (pin "3") (pinfunction "3_3") (pintype "bidirectional"))
    )
    (net (code "91") (name "RTS#") (class "Default")
      (node (ref "C3") (pin "1") (pinfunction "1_1") (pintype "passive"))
      (node (ref "JP3") (pin "6") (pinfunction "6_6") (pintype "passive"))
    )
    (net (code "92") (name "VCC") (class "Default")
      (node (ref "AVCC") (pin "1") (pinfunction "1_1") (pintype "passive"))
      (node (ref "AVCC") (pin "2") (pinfunction "2_2") (pintype "passive"))
      (node (ref "AVCC") (pin "3") (pinfunction "3_3") (pintype "passive"))
      (node (ref "IC1") (pin "20") (pinfunction "AVCC_20") (pintype "bidirectional"))
      (node (ref "IC1") (pin "7") (pinfunction "VCC_7") (pintype "bidirectional"))
      (node (ref "J3") (pin "2") (pinfunction "2_2") (pintype "passive"))
      (node (ref "JP4") (pin "2") (pinfunction "2_2") (pintype "passive"))
      (node (ref "R1") (pin "1") (pinfunction "1_1") (pintype "passive"))
      (node (ref "R2") (pin "2") (pinfunction "2_2") (pintype "passive"))
      (node (ref "U$1") (pin "P$1") (pinfunction "1_P$1") (pintype "passive"))
      (node (ref "U$1") (pin "P$10") (pinfunction "P$10_P$10") (pintype "passive"))
      (node (ref "U$1") (pin "P$2") (pinfunction "5_P$2") (pintype "passive"))
      (node (ref "U$1") (pin "P$3") (pinfunction "P$3_P$3") (pintype "passive"))
      (node (ref "U$1") (pin "P$4") (pinfunction "P$4_P$4") (pintype "passive"))
      (node (ref "U$1") (pin "P$5") (pinfunction "P$5_P$5") (pintype "passive"))
      (node (ref "U$1") (pin "P$6") (pinfunction "P$6_P$6") (pintype "passive"))
      (node (ref "U$1") (pin "P$7") (pinfunction "P$7_P$7") (pintype "passive"))
      (node (ref "U$1") (pin "P$8") (pinfunction "P$8_P$8") (pintype "passive"))
      (node (ref "U$1") (pin "P$9") (pinfunction "P$9_P$9") (pintype "passive"))
      (node (ref "VCC") (pin "1") (pinfunction "1_1") (pintype "passive"))
      (node (ref "VCC") (pin "2") (pinfunction "2_2") (pintype "passive"))
      (node (ref "VCC") (pin "3") (pinfunction "3_3") (pintype "passive"))
    )
    (net (code "93") (name "VIN") (class "Default")
      (node (ref "C1") (pin "1") (pinfunction "+_1") (pintype "passive"))
      (node (ref "IC2") (pin "1") (pinfunction "VI_1") (pintype "input"))
      (node (ref "S1") (pin "3") (pinfunction "S_3") (pintype "passive"))
      (node (ref "VIN") (pin "1") (pinfunction "1_1") (pintype "passive"))
      (node (ref "VIN") (pin "2") (pinfunction "2_2") (pintype "passive"))
      (node (ref "VIN") (pin "3") (pinfunction "3_3") (pintype "passive"))
    )
    (net (code "94") (name "unconnected-(J1-CDN-Pad-2)") (class "Default")
      (node (ref "J1") (pin "-2") (pinfunction "CDN_-2") (pintype "bidirectional"))
    )
    (net (code "95") (name "unconnected-(S1-O-Pad1)") (class "Default")
      (node (ref "S1") (pin "1") (pinfunction "O_1") (pintype "passive"))
    )
  )
)
